# schematic.net
KiCad netlist of a schematic drawn in EasyEDA
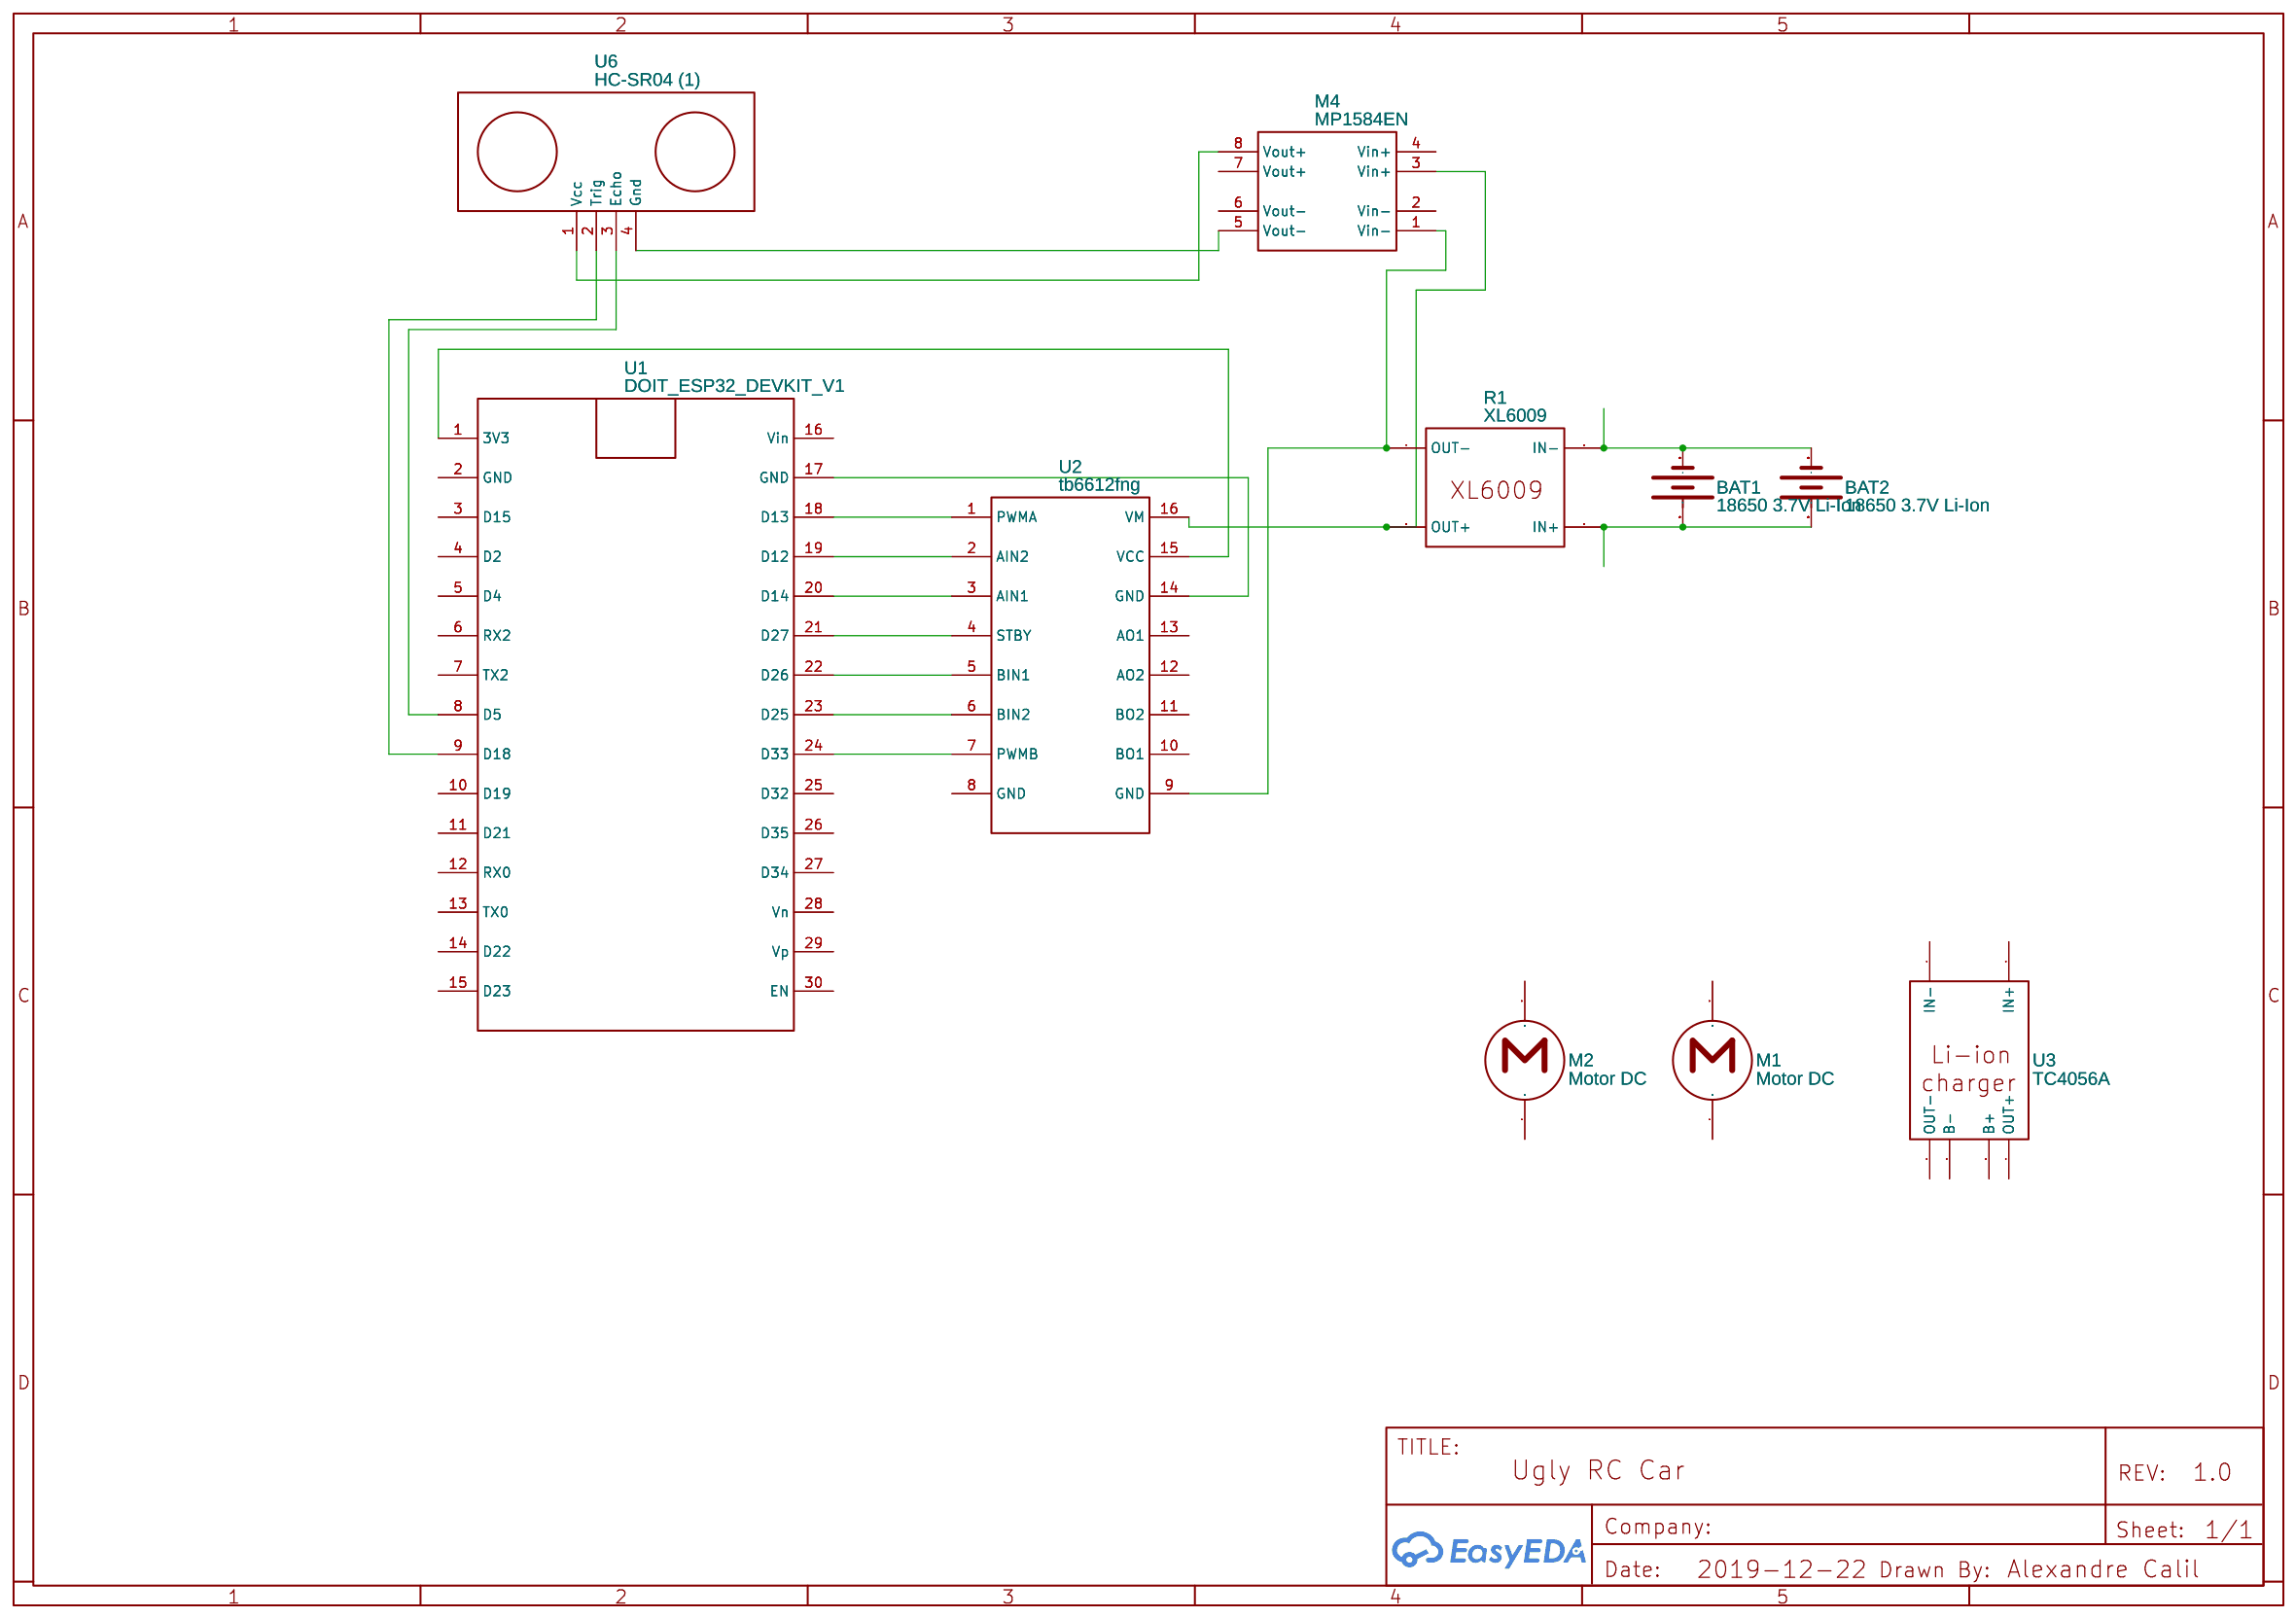
[diagram p0: schematic sheet]

(export (version "E")
  (design (tool "Eeschema 10.0.6"))
  (components
    (comp (ref "BAT1")
      (value "18650 3.7V Li-Ion")
      (fields (field (name "BOM_Supplier Part") "undefined"))
      (libsource (lib "") (part "Unknown_845_260"))
    )
    (comp (ref "BAT2")
      (value "18650 3.7V Li-Ion")
      (fields (field (name "BOM_Supplier Part") "undefined"))
      (libsource (lib "") (part "Unknown_910_260"))
    )
    (comp (ref "M1") (value "Motor DC") (libsource (lib "") (part "Unknown_860_530")))
    (comp (ref "M2") (value "Motor DC") (libsource (lib "") (part "Unknown_765_530")))
    (comp (ref "M4") (value "MP1584EN") (libsource (lib "") (part "Unknown_700_120")))
    (comp (ref "R1") (value "XL6009") (libsource (lib "") (part "XL6009")))
    (comp (ref "U1")
      (value "DOIT_ESP32_DEVKIT_V1")
      (fields (field (name "BOM_Manufacturer Part") "DOIT ESP32 DEVKIT V1"))
      (libsource (lib "") (part "Unknown_315_385"))
    )
    (comp (ref "U2") (value "tb6612fng") (libsource (lib "") (part "Unknown_515_325")))
    (comp (ref "U3") (value "TC4056A") (libsource (lib "") (part "TC4056A_Li_ion_charger")))
    (comp (ref "U6")
      (value "HC-SR04 (1)")
      (fields (field (name "BOM_Manufacturer Part") "HC-SR04"))
      (libsource (lib "") (part "Unknown_285_120"))
    )
  )
  (nets
    (net (code "1") (name "Net-(BAT1-+)") (class "Default")
      (node (ref "BAT1") (pin "PWR@1") (pinfunction "+_PWR@1") (pintype "passive"))
      (node (ref "BAT2") (pin "PWR@1") (pinfunction "+_PWR@1") (pintype "passive"))
      (node (ref "R1") (pin "1") (pinfunction "IN+_1") (pintype "unspecified"))
    )
    (net (code "2") (name "Net-(BAT1--)") (class "Default")
      (node (ref "BAT1") (pin "GND@1") (pinfunction "-_GND@1") (pintype "passive"))
      (node (ref "BAT2") (pin "GND@1") (pinfunction "-_GND@1") (pintype "passive"))
      (node (ref "R1") (pin "2") (pinfunction "IN-_2") (pintype "unspecified"))
    )
    (net (code "3") (name "Net-(R1-OUT+)") (class "Default")
      (node (ref "M4") (pin "3") (pinfunction "Vin+_3") (pintype "unspecified"))
      (node (ref "R1") (pin "3") (pinfunction "OUT+_3") (pintype "unspecified"))
      (node (ref "U2") (pin "16") (pinfunction "VM_16") (pintype "unspecified"))
    )
    (net (code "4") (name "Net-(R1-OUT-)") (class "Default")
      (node (ref "M4") (pin "1") (pinfunction "Vin-_1") (pintype "unspecified"))
      (node (ref "R1") (pin "4") (pinfunction "OUT-_4") (pintype "unspecified"))
      (node (ref "U2") (pin "9") (pinfunction "GND_9") (pintype "unspecified"))
    )
    (net (code "5") (name "Net-(U1-3V3)") (class "Default")
      (node (ref "U1") (pin "1") (pinfunction "3V3_1") (pintype "unspecified"))
      (node (ref "U2") (pin "15") (pinfunction "VCC_15") (pintype "unspecified"))
    )
    (net (code "6") (name "Net-(U1-D5)") (class "Default")
      (node (ref "U1") (pin "8") (pinfunction "D5_8") (pintype "unspecified"))
      (node (ref "U6") (pin "3") (pinfunction "Echo_3") (pintype "unspecified"))
    )
    (net (code "7") (name "Net-(U1-D12)") (class "Default")
      (node (ref "U1") (pin "19") (pinfunction "D12_19") (pintype "unspecified"))
      (node (ref "U2") (pin "2") (pinfunction "AIN2_2") (pintype "unspecified"))
    )
    (net (code "8") (name "Net-(U1-D13)") (class "Default")
      (node (ref "U1") (pin "18") (pinfunction "D13_18") (pintype "unspecified"))
      (node (ref "U2") (pin "1") (pinfunction "PWMA_1") (pintype "unspecified"))
    )
    (net (code "9") (name "Net-(U1-D14)") (class "Default")
      (node (ref "U1") (pin "20") (pinfunction "D14_20") (pintype "unspecified"))
      (node (ref "U2") (pin "3") (pinfunction "AIN1_3") (pintype "unspecified"))
    )
    (net (code "10") (name "Net-(U1-D18)") (class "Default")
      (node (ref "U1") (pin "9") (pinfunction "D18_9") (pintype "unspecified"))
      (node (ref "U6") (pin "2") (pinfunction "Trig_2") (pintype "unspecified"))
    )
    (net (code "11") (name "Net-(U1-D25)") (class "Default")
      (node (ref "U1") (pin "23") (pinfunction "D25_23") (pintype "unspecified"))
      (node (ref "U2") (pin "6") (pinfunction "BIN2_6") (pintype "unspecified"))
    )
    (net (code "12") (name "Net-(U1-D26)") (class "Default")
      (node (ref "U1") (pin "22") (pinfunction "D26_22") (pintype "unspecified"))
      (node (ref "U2") (pin "5") (pinfunction "BIN1_5") (pintype "unspecified"))
    )
    (net (code "13") (name "Net-(U1-D27)") (class "Default")
      (node (ref "U1") (pin "21") (pinfunction "D27_21") (pintype "unspecified"))
      (node (ref "U2") (pin "4") (pinfunction "STBY_4") (pintype "unspecified"))
    )
    (net (code "14") (name "Net-(U1-D33)") (class "Default")
      (node (ref "U1") (pin "24") (pinfunction "D33_24") (pintype "unspecified"))
      (node (ref "U2") (pin "7") (pinfunction "PWMB_7") (pintype "unspecified"))
    )
    (net (code "15") (name "Net-(U1-GND-Pad17)") (class "Default")
      (node (ref "U1") (pin "17") (pinfunction "GND_17") (pintype "unspecified"))
      (node (ref "U2") (pin "14") (pinfunction "GND_14") (pintype "unspecified"))
    )
    (net (code "16") (name "Net-(U6-Gnd)") (class "Default")
      (node (ref "M4") (pin "5") (pinfunction "Vout-_5") (pintype "unspecified"))
      (node (ref "U6") (pin "4") (pinfunction "Gnd_4") (pintype "unspecified"))
    )
    (net (code "17") (name "Net-(U6-Vcc)") (class "Default")
      (node (ref "M4") (pin "8") (pinfunction "Vout+_8") (pintype "unspecified"))
      (node (ref "U6") (pin "1") (pinfunction "Vcc_1") (pintype "unspecified"))
    )
    (net (code "18") (name "unconnected-(M1-Pad1)") (class "Default")
      (node (ref "M1") (pin "1") (pinfunction "1_1") (pintype "unspecified"))
    )
    (net (code "19") (name "unconnected-(M1-Pad2)") (class "Default")
      (node (ref "M1") (pin "2") (pinfunction "2_2") (pintype "unspecified"))
    )
    (net (code "20") (name "unconnected-(M2-Pad1)") (class "Default")
      (node (ref "M2") (pin "1") (pinfunction "1_1") (pintype "unspecified"))
    )
    (net (code "21") (name "unconnected-(M2-Pad2)") (class "Default")
      (node (ref "M2") (pin "2") (pinfunction "2_2") (pintype "unspecified"))
    )
    (net (code "22") (name "unconnected-(M4-Vin+-Pad4)") (class "Default")
      (node (ref "M4") (pin "4") (pinfunction "Vin+_4") (pintype "unspecified"))
    )
    (net (code "23") (name "unconnected-(M4-Vin--Pad2)") (class "Default")
      (node (ref "M4") (pin "2") (pinfunction "Vin-_2") (pintype "unspecified"))
    )
    (net (code "24") (name "unconnected-(M4-Vout+-Pad7)") (class "Default")
      (node (ref "M4") (pin "7") (pinfunction "Vout+_7") (pintype "unspecified"))
    )
    (net (code "25") (name "unconnected-(M4-Vout--Pad6)") (class "Default")
      (node (ref "M4") (pin "6") (pinfunction "Vout-_6") (pintype "unspecified"))
    )
    (net (code "26") (name "unconnected-(U1-D2-Pad4)") (class "Default")
      (node (ref "U1") (pin "4") (pinfunction "D2_4") (pintype "unspecified"))
    )
    (net (code "27") (name "unconnected-(U1-D4-Pad5)") (class "Default")
      (node (ref "U1") (pin "5") (pinfunction "D4_5") (pintype "unspecified"))
    )
    (net (code "28") (name "unconnected-(U1-D15-Pad3)") (class "Default")
      (node (ref "U1") (pin "3") (pinfunction "D15_3") (pintype "unspecified"))
    )
    (net (code "29") (name "unconnected-(U1-D19-Pad10)") (class "Default")
      (node (ref "U1") (pin "10") (pinfunction "D19_10") (pintype "unspecified"))
    )
    (net (code "30") (name "unconnected-(U1-D21-Pad11)") (class "Default")
      (node (ref "U1") (pin "11") (pinfunction "D21_11") (pintype "unspecified"))
    )
    (net (code "31") (name "unconnected-(U1-D22-Pad14)") (class "Default")
      (node (ref "U1") (pin "14") (pinfunction "D22_14") (pintype "unspecified"))
    )
    (net (code "32") (name "unconnected-(U1-D23-Pad15)") (class "Default")
      (node (ref "U1") (pin "15") (pinfunction "D23_15") (pintype "unspecified"))
    )
    (net (code "33") (name "unconnected-(U1-D32-Pad25)") (class "Default")
      (node (ref "U1") (pin "25") (pinfunction "D32_25") (pintype "unspecified"))
    )
    (net (code "34") (name "unconnected-(U1-D34-Pad27)") (class "Default")
      (node (ref "U1") (pin "27") (pinfunction "D34_27") (pintype "unspecified"))
    )
    (net (code "35") (name "unconnected-(U1-D35-Pad26)") (class "Default")
      (node (ref "U1") (pin "26") (pinfunction "D35_26") (pintype "unspecified"))
    )
    (net (code "36") (name "unconnected-(U1-EN-Pad30)") (class "Default")
      (node (ref "U1") (pin "30") (pinfunction "EN_30") (pintype "unspecified"))
    )
    (net (code "37") (name "unconnected-(U1-GND-Pad2)") (class "Default")
      (node (ref "U1") (pin "2") (pinfunction "GND_2") (pintype "unspecified"))
    )
    (net (code "38") (name "unconnected-(U1-RX0-Pad12)") (class "Default")
      (node (ref "U1") (pin "12") (pinfunction "RX0_12") (pintype "unspecified"))
    )
    (net (code "39") (name "unconnected-(U1-RX2-Pad6)") (class "Default")
      (node (ref "U1") (pin "6") (pinfunction "RX2_6") (pintype "unspecified"))
    )
    (net (code "40") (name "unconnected-(U1-TX0-Pad13)") (class "Default")
      (node (ref "U1") (pin "13") (pinfunction "TX0_13") (pintype "unspecified"))
    )
    (net (code "41") (name "unconnected-(U1-TX2-Pad7)") (class "Default")
      (node (ref "U1") (pin "7") (pinfunction "TX2_7") (pintype "unspecified"))
    )
    (net (code "42") (name "unconnected-(U1-Vin-Pad16)") (class "Default")
      (node (ref "U1") (pin "16") (pinfunction "Vin_16") (pintype "unspecified"))
    )
    (net (code "43") (name "unconnected-(U1-Vn-Pad28)") (class "Default")
      (node (ref "U1") (pin "28") (pinfunction "Vn_28") (pintype "unspecified"))
    )
    (net (code "44") (name "unconnected-(U1-Vp-Pad29)") (class "Default")
      (node (ref "U1") (pin "29") (pinfunction "Vp_29") (pintype "unspecified"))
    )
    (net (code "45") (name "unconnected-(U2-AO1-Pad13)") (class "Default")
      (node (ref "U2") (pin "13") (pinfunction "AO1_13") (pintype "unspecified"))
    )
    (net (code "46") (name "unconnected-(U2-AO2-Pad12)") (class "Default")
      (node (ref "U2") (pin "12") (pinfunction "AO2_12") (pintype "unspecified"))
    )
    (net (code "47") (name "unconnected-(U2-BO1-Pad10)") (class "Default")
      (node (ref "U2") (pin "10") (pinfunction "BO1_10") (pintype "unspecified"))
    )
    (net (code "48") (name "unconnected-(U2-BO2-Pad11)") (class "Default")
      (node (ref "U2") (pin "11") (pinfunction "BO2_11") (pintype "unspecified"))
    )
    (net (code "49") (name "unconnected-(U2-GND-Pad8)") (class "Default")
      (node (ref "U2") (pin "8") (pinfunction "GND_8") (pintype "unspecified"))
    )
    (net (code "50") (name "unconnected-(U3-B+-Pad3)") (class "Default")
      (node (ref "U3") (pin "3") (pinfunction "B+_3") (pintype "input"))
    )
    (net (code "51") (name "unconnected-(U3-B--Pad2)") (class "Default")
      (node (ref "U3") (pin "2") (pinfunction "B-_2") (pintype "input"))
    )
    (net (code "52") (name "unconnected-(U3-IN+-Pad1)") (class "Default")
      (node (ref "U3") (pin "1") (pinfunction "IN+_1") (pintype "output"))
    )
    (net (code "53") (name "unconnected-(U3-IN--Pad4)") (class "Default")
      (node (ref "U3") (pin "4") (pinfunction "IN-_4") (pintype "output"))
    )
    (net (code "54") (name "unconnected-(U3-OUT+-Pad4)") (class "Default")
      (node (ref "U3") (pin "4") (pinfunction "OUT+_4") (pintype "output"))
    )
    (net (code "55") (name "unconnected-(U3-OUT--Pad1)") (class "Default")
      (node (ref "U3") (pin "1") (pinfunction "OUT-_1") (pintype "output"))
    )
  )
)
